# FlasherSchematic.net
KiCad netlist of a schematic drawn in EAGLE
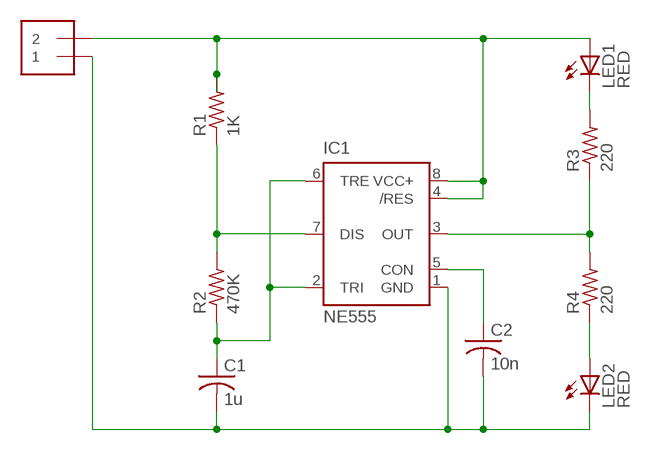
[diagram p0: schematic, sheet 1]

(export (version "E")
  (design (tool "Eeschema 10.0.6"))
  (components
    (comp (ref "C1")
      (value "1u")
      (footprint "eagle-import:C0805")
      (libsource (lib "eagle-import") (part "C-USC0805"))
    )
    (comp (ref "C2")
      (value "10n")
      (footprint "eagle-import:C0805")
      (libsource (lib "eagle-import") (part "C-USC0805"))
    )
    (comp (ref "IC1")
      (value "NE555")
      (footprint "eagle-import:DIL-08")
      (fields (field (name "MF") "Arrow Electronics") (field (name "MPN") "NE555N"))
      (libsource (lib "eagle-import") (part "NE555"))
    )
    (comp (ref "J1")
      (value "1X2-3.5MM")
      (footprint "eagle-import:1X2-3.5MM")
      (libsource (lib "eagle-import") (part "1X2-3.5MM"))
    )
    (comp (ref "LED1")
      (value "RED")
      (footprint "eagle-import:CHIP-LED0805")
      (libsource (lib "eagle-import") (part "LEDCHIP-LED0805"))
    )
    (comp (ref "LED2")
      (value "RED")
      (footprint "eagle-import:CHIP-LED0805")
      (libsource (lib "eagle-import") (part "LEDCHIP-LED0805"))
    )
    (comp (ref "R1")
      (value "1K")
      (footprint "eagle-import:M0805")
      (libsource (lib "eagle-import") (part "R-US_M0805"))
    )
    (comp (ref "R2")
      (value "470K")
      (footprint "eagle-import:M0805")
      (libsource (lib "eagle-import") (part "R-US_M0805"))
    )
    (comp (ref "R3")
      (value "220")
      (footprint "eagle-import:M0805")
      (libsource (lib "eagle-import") (part "R-US_M0805"))
    )
    (comp (ref "R4")
      (value "220")
      (footprint "eagle-import:M0805")
      (libsource (lib "eagle-import") (part "R-US_M0805"))
    )
  )
  (nets
    (net (code "1") (name "Net-(IC1-CON)") (class "Default")
      (node (ref "C2") (pin "1") (pinfunction "1_1") (pintype "passive"))
      (node (ref "IC1") (pin "5") (pinfunction "CON_5") (pintype "input"))
    )
    (net (code "2") (name "Net-(IC1-DIS)") (class "Default")
      (node (ref "IC1") (pin "7") (pinfunction "DIS_7") (pintype "input"))
      (node (ref "R1") (pin "1") (pinfunction "1_1") (pintype "passive"))
      (node (ref "R2") (pin "2") (pinfunction "2_2") (pintype "passive"))
    )
    (net (code "3") (name "Net-(IC1-GND)") (class "Default")
      (node (ref "C1") (pin "2") (pinfunction "2_2") (pintype "passive"))
      (node (ref "C2") (pin "2") (pinfunction "2_2") (pintype "passive"))
      (node (ref "IC1") (pin "1") (pinfunction "GND_1") (pintype "power_in"))
      (node (ref "J1") (pin "1") (pinfunction "1_1") (pintype "passive"))
      (node (ref "LED2") (pin "C") (pinfunction "C_C") (pintype "passive"))
    )
    (net (code "4") (name "Net-(IC1-OUT)") (class "Default")
      (node (ref "IC1") (pin "3") (pinfunction "OUT_3") (pintype "output"))
      (node (ref "R3") (pin "1") (pinfunction "1_1") (pintype "passive"))
      (node (ref "R4") (pin "2") (pinfunction "2_2") (pintype "passive"))
    )
    (net (code "5") (name "Net-(IC1-TRE)") (class "Default")
      (node (ref "C1") (pin "1") (pinfunction "1_1") (pintype "passive"))
      (node (ref "IC1") (pin "2") (pinfunction "TRI_2") (pintype "input"))
      (node (ref "IC1") (pin "6") (pinfunction "TRE_6") (pintype "input"))
      (node (ref "R2") (pin "1") (pinfunction "1_1") (pintype "passive"))
    )
    (net (code "6") (name "Net-(IC1-VCC+)") (class "Default")
      (node (ref "IC1") (pin "4") (pinfunction "/RES_4") (pintype "input"))
      (node (ref "IC1") (pin "8") (pinfunction "VCC+_8") (pintype "power_in"))
      (node (ref "J1") (pin "2") (pinfunction "2_2") (pintype "passive"))
      (node (ref "LED1") (pin "A") (pinfunction "A_A") (pintype "passive"))
      (node (ref "R1") (pin "2") (pinfunction "2_2") (pintype "passive"))
    )
    (net (code "7") (name "Net-(LED1-PadC)") (class "Default")
      (node (ref "LED1") (pin "C") (pinfunction "C_C") (pintype "passive"))
      (node (ref "R3") (pin "2") (pinfunction "2_2") (pintype "passive"))
    )
    (net (code "8") (name "Net-(LED2-PadA)") (class "Default")
      (node (ref "LED2") (pin "A") (pinfunction "A_A") (pintype "passive"))
      (node (ref "R4") (pin "1") (pinfunction "1_1") (pintype "passive"))
    )
  )
)
